# Schematic_v3.net
KiCad netlist of a schematic drawn in EAGLE
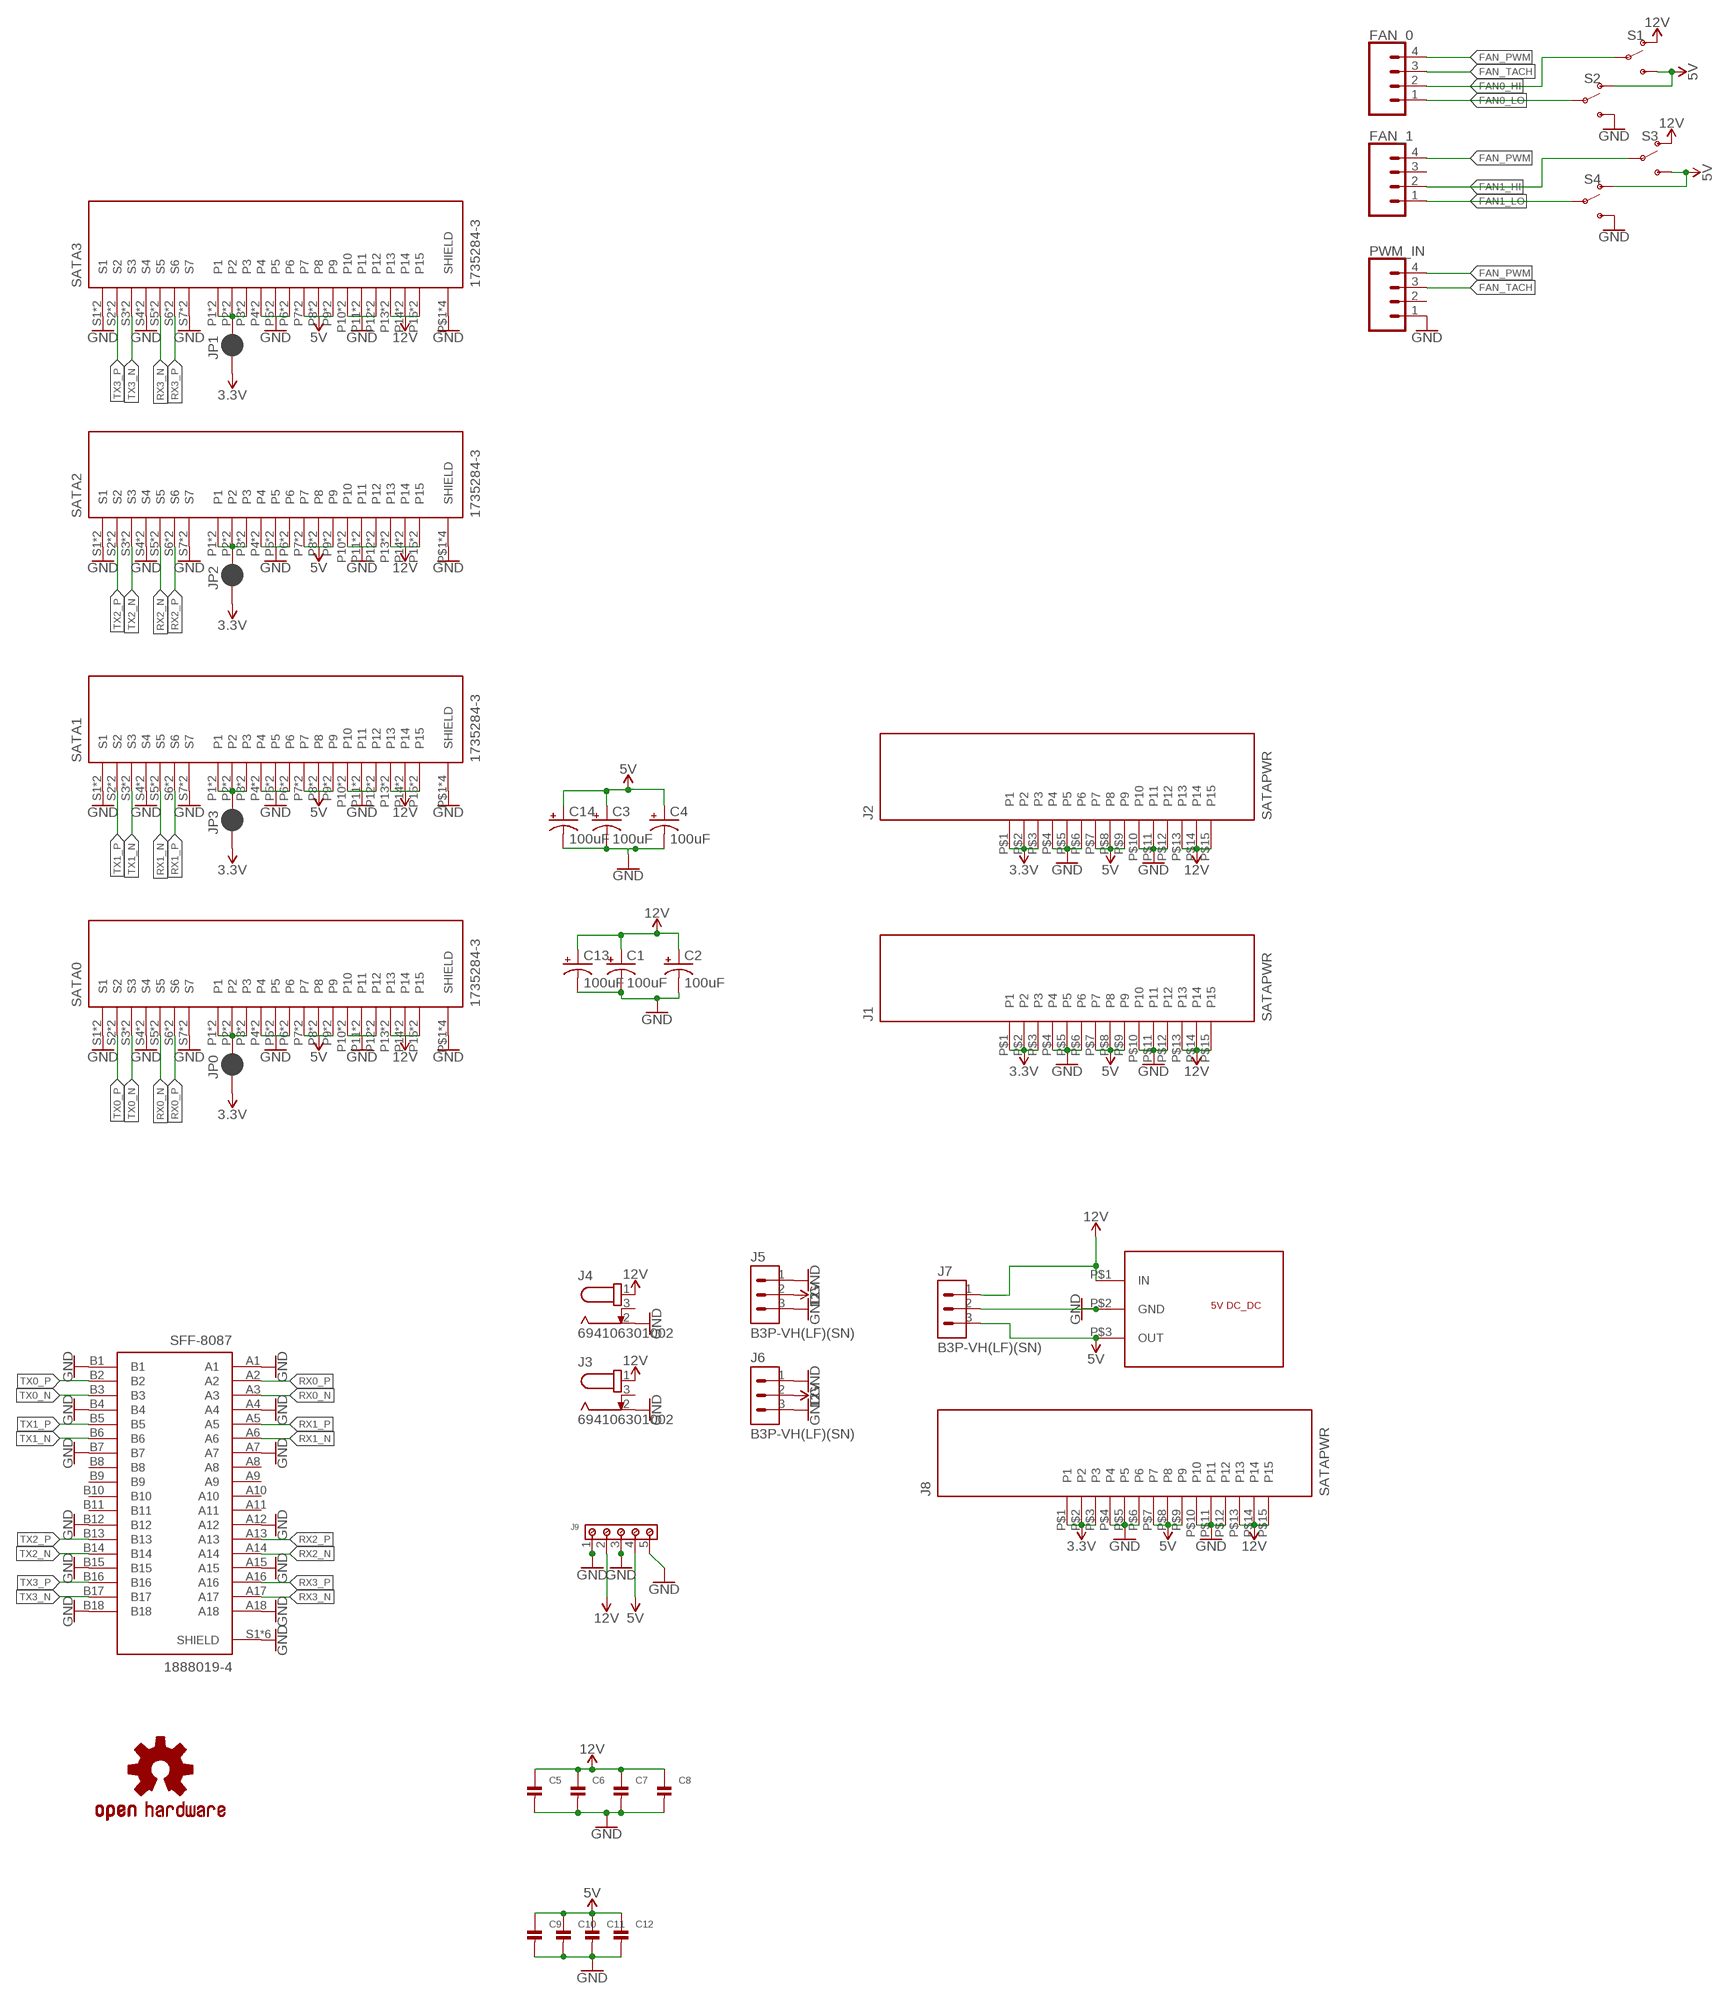
[diagram p0: schematic, sheet 1]

(export (version "E")
  (design (tool "Eeschema 10.0.6"))
  (components
    (comp (ref "C1")
      (value "100uF")
      (footprint "eagle-import:PANASONIC_D")
      (libsource (lib "eagle-import") (part "100UF-POLAR-25V-20%(ELEC)"))
    )
    (comp (ref "C2")
      (value "100uF")
      (footprint "eagle-import:PANASONIC_D")
      (libsource (lib "eagle-import") (part "100UF-POLAR-25V-20%(ELEC)"))
    )
    (comp (ref "C3")
      (value "100uF")
      (footprint "eagle-import:PANASONIC_D")
      (libsource (lib "eagle-import") (part "100UF-POLAR-25V-20%(ELEC)"))
    )
    (comp (ref "C4")
      (value "100uF")
      (footprint "eagle-import:PANASONIC_D")
      (libsource (lib "eagle-import") (part "100UF-POLAR-25V-20%(ELEC)"))
    )
    (comp (ref "C5")
      (value "CAP_CERAMIC0805")
      (footprint "eagle-import:C0805")
      (libsource (lib "eagle-import") (part "CAP_CERAMIC0805"))
    )
    (comp (ref "C6")
      (value "CAP_CERAMIC0805")
      (footprint "eagle-import:C0805")
      (libsource (lib "eagle-import") (part "CAP_CERAMIC0805"))
    )
    (comp (ref "C7")
      (value "CAP_CERAMIC0805")
      (footprint "eagle-import:C0805")
      (libsource (lib "eagle-import") (part "CAP_CERAMIC0805"))
    )
    (comp (ref "C8")
      (value "CAP_CERAMIC0805")
      (footprint "eagle-import:C0805")
      (libsource (lib "eagle-import") (part "CAP_CERAMIC0805"))
    )
    (comp (ref "C9")
      (value "CAP_CERAMIC0805")
      (footprint "eagle-import:C0805")
      (libsource (lib "eagle-import") (part "CAP_CERAMIC0805"))
    )
    (comp (ref "C10")
      (value "CAP_CERAMIC0805")
      (footprint "eagle-import:C0805")
      (libsource (lib "eagle-import") (part "CAP_CERAMIC0805"))
    )
    (comp (ref "C11")
      (value "CAP_CERAMIC0805")
      (footprint "eagle-import:C0805")
      (libsource (lib "eagle-import") (part "CAP_CERAMIC0805"))
    )
    (comp (ref "C12")
      (value "CAP_CERAMIC0805")
      (footprint "eagle-import:C0805")
      (libsource (lib "eagle-import") (part "CAP_CERAMIC0805"))
    )
    (comp (ref "C13")
      (value "100uF")
      (footprint "eagle-import:PANASONIC_D")
      (libsource (lib "eagle-import") (part "100UF-POLAR-25V-20%(ELEC)"))
    )
    (comp (ref "C14")
      (value "100uF")
      (footprint "eagle-import:PANASONIC_D")
      (libsource (lib "eagle-import") (part "100UF-POLAR-25V-20%(ELEC)"))
    )
    (comp (ref "FAN_0")
      (value "CONN_04POLAR_LOCK")
      (footprint "eagle-import:MOLEX-1X4_LOCK")
      (libsource (lib "eagle-import") (part "CONN_04POLAR_LOCK"))
    )
    (comp (ref "FAN_1")
      (value "CONN_04POLAR_LOCK")
      (footprint "eagle-import:MOLEX-1X4_LOCK")
      (libsource (lib "eagle-import") (part "CONN_04POLAR_LOCK"))
    )
    (comp (ref "J1")
      (value "SATAPWR")
      (footprint "eagle-import:PTH_90")
      (libsource (lib "eagle-import") (part "SATAPWR"))
    )
    (comp (ref "J2")
      (value "SATAPWR")
      (footprint "eagle-import:PTH_90")
      (libsource (lib "eagle-import") (part "SATAPWR"))
    )
    (comp (ref "J3")
      (value "694106301002")
      (footprint "eagle-import:694106301002")
      (fields
        (field (name "DIGIKEY_PART_NUMBER") "732-5930-ND")
        (field (name "MANUFACTURER") "Wurth Electronics Inc.")
        (field (name "CREATED_BY") "PCBLayout.com")
      )
      (libsource (lib "eagle-import") (part "694106301002"))
    )
    (comp (ref "J4")
      (value "694106301002")
      (footprint "eagle-import:694106301002")
      (fields
        (field (name "DIGIKEY_PART_NUMBER") "732-5930-ND")
        (field (name "MANUFACTURER") "Wurth Electronics Inc.")
        (field (name "CREATED_BY") "PCBLayout.com")
      )
      (libsource (lib "eagle-import") (part "694106301002"))
    )
    (comp (ref "J5")
      (value "B3P-VH(LF)(SN)")
      (footprint "eagle-import:HDR-03")
      (fields
        (field (name "DIGIKEY_PART_NUMBER") "455-1640-ND")
        (field (name "MANUFACTURER") "JST Sales America Inc.")
        (field (name "CREATED_BY") "PCBLayout.com")
      )
      (libsource (lib "eagle-import") (part "B3P-VH(LF)(SN)"))
    )
    (comp (ref "J6")
      (value "B3P-VH(LF)(SN)")
      (footprint "eagle-import:HDR-03")
      (fields
        (field (name "DIGIKEY_PART_NUMBER") "455-1640-ND")
        (field (name "MANUFACTURER") "JST Sales America Inc.")
        (field (name "CREATED_BY") "PCBLayout.com")
      )
      (libsource (lib "eagle-import") (part "B3P-VH(LF)(SN)"))
    )
    (comp (ref "J7")
      (value "B3P-VH(LF)(SN)")
      (footprint "eagle-import:HDR-03")
      (fields
        (field (name "DIGIKEY_PART_NUMBER") "455-1640-ND")
        (field (name "MANUFACTURER") "JST Sales America Inc.")
        (field (name "CREATED_BY") "PCBLayout.com")
      )
      (libsource (lib "eagle-import") (part "B3P-VH(LF)(SN)"))
    )
    (comp (ref "J8")
      (value "SATAPWR")
      (footprint "eagle-import:PTH_90")
      (libsource (lib "eagle-import") (part "SATAPWR"))
    )
    (comp (ref "J9")
      (value "691243410005")
      (footprint "eagle-import:691243410005")
      (libsource (lib "eagle-import") (part "691243410005"))
    )
    (comp (ref "JP0")
      (value "JUMPER-SMT_2_NC_PASTE_SILK")
      (footprint "eagle-import:SMT-JUMPER_2_NC_PASTE_SILK")
      (libsource (lib "eagle-import") (part "JUMPER-SMT_2_NC_PASTE_SILK"))
    )
    (comp (ref "JP1")
      (value "JUMPER-SMT_2_NC_PASTE_SILK")
      (footprint "eagle-import:SMT-JUMPER_2_NC_PASTE_SILK")
      (libsource (lib "eagle-import") (part "JUMPER-SMT_2_NC_PASTE_SILK"))
    )
    (comp (ref "JP2")
      (value "JUMPER-SMT_2_NC_PASTE_SILK")
      (footprint "eagle-import:SMT-JUMPER_2_NC_PASTE_SILK")
      (libsource (lib "eagle-import") (part "JUMPER-SMT_2_NC_PASTE_SILK"))
    )
    (comp (ref "JP3")
      (value "JUMPER-SMT_2_NC_PASTE_SILK")
      (footprint "eagle-import:SMT-JUMPER_2_NC_PASTE_SILK")
      (libsource (lib "eagle-import") (part "JUMPER-SMT_2_NC_PASTE_SILK"))
    )
    (comp (ref "LOGO1")
      (value "OSHW-LOGOL")
      (footprint "eagle-import:OSHW-LOGO-L")
      (libsource (lib "eagle-import") (part "OSHW-LOGOL"))
    )
    (comp (ref "PWM_IN")
      (value "CONN_04POLAR_LOCK")
      (footprint "eagle-import:MOLEX-1X4_LOCK")
      (libsource (lib "eagle-import") (part "CONN_04POLAR_LOCK"))
    )
    (comp (ref "S1")
      (value "SWITCH-SPDT-PTH-11.6X4.0MM-LOCK")
      (footprint "eagle-import:SWITCH_SPDT_PTH_11.6X4.0MM_LOCK")
      (libsource (lib "eagle-import") (part "SWITCH-SPDT-PTH-11.6X4.0MM-LOCK"))
    )
    (comp (ref "S2")
      (value "SWITCH-SPDT-PTH-11.6X4.0MM-LOCK")
      (footprint "eagle-import:SWITCH_SPDT_PTH_11.6X4.0MM_LOCK")
      (libsource (lib "eagle-import") (part "SWITCH-SPDT-PTH-11.6X4.0MM-LOCK"))
    )
    (comp (ref "S3")
      (value "SWITCH-SPDT-PTH-11.6X4.0MM-LOCK")
      (footprint "eagle-import:SWITCH_SPDT_PTH_11.6X4.0MM_LOCK")
      (libsource (lib "eagle-import") (part "SWITCH-SPDT-PTH-11.6X4.0MM-LOCK"))
    )
    (comp (ref "S4")
      (value "SWITCH-SPDT-PTH-11.6X4.0MM-LOCK")
      (footprint "eagle-import:SWITCH_SPDT_PTH_11.6X4.0MM_LOCK")
      (libsource (lib "eagle-import") (part "SWITCH-SPDT-PTH-11.6X4.0MM-LOCK"))
    )
    (comp (ref "SATA0")
      (value "1735284-3")
      (footprint "eagle-import:TE_2023246-2")
      (fields (field (name "COMMENT") "2023246-2") (field (name "MF") "TE Connectivity"))
      (libsource (lib "eagle-import") (part "2023246-21735284-3"))
    )
    (comp (ref "SATA1")
      (value "1735284-3")
      (footprint "eagle-import:TE_2023246-2")
      (fields (field (name "COMMENT") "2023246-2") (field (name "MF") "TE Connectivity"))
      (libsource (lib "eagle-import") (part "2023246-21735284-3"))
    )
    (comp (ref "SATA2")
      (value "1735284-3")
      (footprint "eagle-import:TE_2023246-2")
      (fields (field (name "COMMENT") "2023246-2") (field (name "MF") "TE Connectivity"))
      (libsource (lib "eagle-import") (part "2023246-21735284-3"))
    )
    (comp (ref "SATA3")
      (value "1735284-3")
      (footprint "eagle-import:TE_2023246-2")
      (fields (field (name "COMMENT") "2023246-2") (field (name "MF") "TE Connectivity"))
      (libsource (lib "eagle-import") (part "2023246-21735284-3"))
    )
    (comp (ref "SFF-8087")
      (value "1888019-4")
      (footprint "eagle-import:TE_1888019-4")
      (fields (field (name "MF") "TE Connectivity"))
      (libsource (lib "eagle-import") (part "1888019-4"))
    )
    (comp (ref "U$1")
      (value "5V_DC_DC")
      (footprint "eagle-import:5V_15W_DC_DC")
      (libsource (lib "eagle-import") (part "5V_DC_DC"))
    )
  )
  (nets
    (net (code "1") (name "3.3V") (class "Default")
      (node (ref "J1") (pin "P$1") (pinfunction "P1_P$1") (pintype "passive"))
      (node (ref "J1") (pin "P$2") (pinfunction "P2_P$2") (pintype "passive"))
      (node (ref "J1") (pin "P$3") (pinfunction "P3_P$3") (pintype "passive"))
      (node (ref "J2") (pin "P$1") (pinfunction "P1_P$1") (pintype "passive"))
      (node (ref "J2") (pin "P$2") (pinfunction "P2_P$2") (pintype "passive"))
      (node (ref "J2") (pin "P$3") (pinfunction "P3_P$3") (pintype "passive"))
      (node (ref "J8") (pin "P$1") (pinfunction "P1_P$1") (pintype "passive"))
      (node (ref "J8") (pin "P$2") (pinfunction "P2_P$2") (pintype "passive"))
      (node (ref "J8") (pin "P$3") (pinfunction "P3_P$3") (pintype "passive"))
      (node (ref "JP0") (pin "1") (pinfunction "1_1") (pintype "passive"))
      (node (ref "JP1") (pin "1") (pinfunction "1_1") (pintype "passive"))
      (node (ref "JP2") (pin "1") (pinfunction "1_1") (pintype "passive"))
      (node (ref "JP3") (pin "1") (pinfunction "1_1") (pintype "passive"))
    )
    (net (code "2") (name "5V") (class "Default")
      (node (ref "C10") (pin "1") (pinfunction "P$1_1") (pintype "passive"))
      (node (ref "C11") (pin "1") (pinfunction "P$1_1") (pintype "passive"))
      (node (ref "C12") (pin "1") (pinfunction "P$1_1") (pintype "passive"))
      (node (ref "C14") (pin "+") (pinfunction "+_+") (pintype "passive"))
      (node (ref "C3") (pin "+") (pinfunction "+_+") (pintype "passive"))
      (node (ref "C4") (pin "+") (pinfunction "+_+") (pintype "passive"))
      (node (ref "C9") (pin "1") (pinfunction "P$1_1") (pintype "passive"))
      (node (ref "J1") (pin "P$7") (pinfunction "P7_P$7") (pintype "passive"))
      (node (ref "J1") (pin "P$8") (pinfunction "P8_P$8") (pintype "passive"))
      (node (ref "J1") (pin "P$9") (pinfunction "P9_P$9") (pintype "passive"))
      (node (ref "J2") (pin "P$7") (pinfunction "P7_P$7") (pintype "passive"))
      (node (ref "J2") (pin "P$8") (pinfunction "P8_P$8") (pintype "passive"))
      (node (ref "J2") (pin "P$9") (pinfunction "P9_P$9") (pintype "passive"))
      (node (ref "J7") (pin "3") (pinfunction "3_3") (pintype "passive"))
      (node (ref "J8") (pin "P$7") (pinfunction "P7_P$7") (pintype "passive"))
      (node (ref "J8") (pin "P$8") (pinfunction "P8_P$8") (pintype "passive"))
      (node (ref "J8") (pin "P$9") (pinfunction "P9_P$9") (pintype "passive"))
      (node (ref "J9") (pin "4") (pinfunction "4_4") (pintype "passive"))
      (node (ref "S1") (pin "3") (pinfunction "S_3") (pintype "passive"))
      (node (ref "S2") (pin "1") (pinfunction "O_1") (pintype "passive"))
      (node (ref "S3") (pin "3") (pinfunction "S_3") (pintype "passive"))
      (node (ref "S4") (pin "1") (pinfunction "O_1") (pintype "passive"))
      (node (ref "SATA0") (pin "P7") (pinfunction "P7_P7") (pintype "passive"))
      (node (ref "SATA0") (pin "P8") (pinfunction "P8_P8") (pintype "passive"))
      (node (ref "SATA0") (pin "P9") (pinfunction "P9_P9") (pintype "passive"))
      (node (ref "SATA0") (pin "THT14") (pinfunction "P7_THT14") (pintype "passive"))
      (node (ref "SATA0") (pin "THT15") (pinfunction "P8_THT15") (pintype "passive"))
      (node (ref "SATA0") (pin "THT16") (pinfunction "P9_THT16") (pintype "passive"))
      (node (ref "SATA1") (pin "P7") (pinfunction "P7_P7") (pintype "passive"))
      (node (ref "SATA1") (pin "P8") (pinfunction "P8_P8") (pintype "passive"))
      (node (ref "SATA1") (pin "P9") (pinfunction "P9_P9") (pintype "passive"))
      (node (ref "SATA1") (pin "THT14") (pinfunction "P7_THT14") (pintype "passive"))
      (node (ref "SATA1") (pin "THT15") (pinfunction "P8_THT15") (pintype "passive"))
      (node (ref "SATA1") (pin "THT16") (pinfunction "P9_THT16") (pintype "passive"))
      (node (ref "SATA2") (pin "P7") (pinfunction "P7_P7") (pintype "passive"))
      (node (ref "SATA2") (pin "P8") (pinfunction "P8_P8") (pintype "passive"))
      (node (ref "SATA2") (pin "P9") (pinfunction "P9_P9") (pintype "passive"))
      (node (ref "SATA2") (pin "THT14") (pinfunction "P7_THT14") (pintype "passive"))
      (node (ref "SATA2") (pin "THT15") (pinfunction "P8_THT15") (pintype "passive"))
      (node (ref "SATA2") (pin "THT16") (pinfunction "P9_THT16") (pintype "passive"))
      (node (ref "SATA3") (pin "P7") (pinfunction "P7_P7") (pintype "passive"))
      (node (ref "SATA3") (pin "P8") (pinfunction "P8_P8") (pintype "passive"))
      (node (ref "SATA3") (pin "P9") (pinfunction "P9_P9") (pintype "passive"))
      (node (ref "SATA3") (pin "THT14") (pinfunction "P7_THT14") (pintype "passive"))
      (node (ref "SATA3") (pin "THT15") (pinfunction "P8_THT15") (pintype "passive"))
      (node (ref "SATA3") (pin "THT16") (pinfunction "P9_THT16") (pintype "passive"))
      (node (ref "U$1") (pin "P$3") (pinfunction "OUT_P$3") (pintype "bidirectional"))
    )
    (net (code "3") (name "12V") (class "Default")
      (node (ref "C1") (pin "+") (pinfunction "+_+") (pintype "passive"))
      (node (ref "C13") (pin "+") (pinfunction "+_+") (pintype "passive"))
      (node (ref "C2") (pin "+") (pinfunction "+_+") (pintype "passive"))
      (node (ref "C5") (pin "1") (pinfunction "P$1_1") (pintype "passive"))
      (node (ref "C6") (pin "1") (pinfunction "P$1_1") (pintype "passive"))
      (node (ref "C7") (pin "1") (pinfunction "P$1_1") (pintype "passive"))
      (node (ref "C8") (pin "1") (pinfunction "P$1_1") (pintype "passive"))
      (node (ref "J1") (pin "P$13") (pinfunction "P13_P$13") (pintype "passive"))
      (node (ref "J1") (pin "P$14") (pinfunction "P14_P$14") (pintype "passive"))
      (node (ref "J1") (pin "P$15") (pinfunction "P15_P$15") (pintype "passive"))
      (node (ref "J2") (pin "P$13") (pinfunction "P13_P$13") (pintype "passive"))
      (node (ref "J2") (pin "P$14") (pinfunction "P14_P$14") (pintype "passive"))
      (node (ref "J2") (pin "P$15") (pinfunction "P15_P$15") (pintype "passive"))
      (node (ref "J3") (pin "1") (pinfunction "1_1") (pintype "passive"))
      (node (ref "J4") (pin "1") (pinfunction "1_1") (pintype "passive"))
      (node (ref "J5") (pin "2") (pinfunction "2_2") (pintype "passive"))
      (node (ref "J6") (pin "2") (pinfunction "2_2") (pintype "passive"))
      (node (ref "J7") (pin "1") (pinfunction "1_1") (pintype "passive"))
      (node (ref "J8") (pin "P$13") (pinfunction "P13_P$13") (pintype "passive"))
      (node (ref "J8") (pin "P$14") (pinfunction "P14_P$14") (pintype "passive"))
      (node (ref "J8") (pin "P$15") (pinfunction "P15_P$15") (pintype "passive"))
      (node (ref "J9") (pin "2") (pinfunction "2_2") (pintype "passive"))
      (node (ref "S1") (pin "1") (pinfunction "O_1") (pintype "passive"))
      (node (ref "S3") (pin "1") (pinfunction "O_1") (pintype "passive"))
      (node (ref "SATA0") (pin "P13") (pinfunction "P13_P13") (pintype "passive"))
      (node (ref "SATA0") (pin "P14") (pinfunction "P14_P14") (pintype "passive"))
      (node (ref "SATA0") (pin "P15") (pinfunction "P15_P15") (pintype "passive"))
      (node (ref "SATA0") (pin "THT20") (pinfunction "P13_THT20") (pintype "passive"))
      (node (ref "SATA0") (pin "THT21") (pinfunction "P14_THT21") (pintype "passive"))
      (node (ref "SATA0") (pin "THT22") (pinfunction "P15_THT22") (pintype "passive"))
      (node (ref "SATA1") (pin "P13") (pinfunction "P13_P13") (pintype "passive"))
      (node (ref "SATA1") (pin "P14") (pinfunction "P14_P14") (pintype "passive"))
      (node (ref "SATA1") (pin "P15") (pinfunction "P15_P15") (pintype "passive"))
      (node (ref "SATA1") (pin "THT20") (pinfunction "P13_THT20") (pintype "passive"))
      (node (ref "SATA1") (pin "THT21") (pinfunction "P14_THT21") (pintype "passive"))
      (node (ref "SATA1") (pin "THT22") (pinfunction "P15_THT22") (pintype "passive"))
      (node (ref "SATA2") (pin "P13") (pinfunction "P13_P13") (pintype "passive"))
      (node (ref "SATA2") (pin "P14") (pinfunction "P14_P14") (pintype "passive"))
      (node (ref "SATA2") (pin "P15") (pinfunction "P15_P15") (pintype "passive"))
      (node (ref "SATA2") (pin "THT20") (pinfunction "P13_THT20") (pintype "passive"))
      (node (ref "SATA2") (pin "THT21") (pinfunction "P14_THT21") (pintype "passive"))
      (node (ref "SATA2") (pin "THT22") (pinfunction "P15_THT22") (pintype "passive"))
      (node (ref "SATA3") (pin "P13") (pinfunction "P13_P13") (pintype "passive"))
      (node (ref "SATA3") (pin "P14") (pinfunction "P14_P14") (pintype "passive"))
      (node (ref "SATA3") (pin "P15") (pinfunction "P15_P15") (pintype "passive"))
      (node (ref "SATA3") (pin "THT20") (pinfunction "P13_THT20") (pintype "passive"))
      (node (ref "SATA3") (pin "THT21") (pinfunction "P14_THT21") (pintype "passive"))
      (node (ref "SATA3") (pin "THT22") (pinfunction "P15_THT22") (pintype "passive"))
      (node (ref "U$1") (pin "P$1") (pinfunction "IN_P$1") (pintype "bidirectional"))
    )
    (net (code "4") (name "FAN0_HI") (class "Default")
      (node (ref "FAN_0") (pin "2") (pinfunction "2_2") (pintype "passive"))
      (node (ref "S1") (pin "2") (pinfunction "P_2") (pintype "passive"))
    )
    (net (code "5") (name "FAN0_LO") (class "Default")
      (node (ref "FAN_0") (pin "1") (pinfunction "1_1") (pintype "passive"))
      (node (ref "S2") (pin "2") (pinfunction "P_2") (pintype "passive"))
    )
    (net (code "6") (name "FAN1_HI") (class "Default")
      (node (ref "FAN_1") (pin "2") (pinfunction "2_2") (pintype "passive"))
      (node (ref "S3") (pin "2") (pinfunction "P_2") (pintype "passive"))
    )
    (net (code "7") (name "FAN1_LO") (class "Default")
      (node (ref "FAN_1") (pin "1") (pinfunction "1_1") (pintype "passive"))
      (node (ref "S4") (pin "2") (pinfunction "P_2") (pintype "passive"))
    )
    (net (code "8") (name "FAN_PWM") (class "Default")
      (node (ref "FAN_0") (pin "4") (pinfunction "4_4") (pintype "passive"))
      (node (ref "FAN_1") (pin "4") (pinfunction "4_4") (pintype "passive"))
      (node (ref "PWM_IN") (pin "4") (pinfunction "4_4") (pintype "passive"))
    )
    (net (code "9") (name "FAN_TACH") (class "Default")
      (node (ref "FAN_0") (pin "3") (pinfunction "3_3") (pintype "passive"))
      (node (ref "PWM_IN") (pin "3") (pinfunction "3_3") (pintype "passive"))
    )
    (net (code "10") (name "GND") (class "Default")
      (node (ref "C1") (pin "-") (pinfunction "-_-") (pintype "passive"))
      (node (ref "C10") (pin "2") (pinfunction "P$2_2") (pintype "passive"))
      (node (ref "C11") (pin "2") (pinfunction "P$2_2") (pintype "passive"))
      (node (ref "C12") (pin "2") (pinfunction "P$2_2") (pintype "passive"))
      (node (ref "C13") (pin "-") (pinfunction "-_-") (pintype "passive"))
      (node (ref "C14") (pin "-") (pinfunction "-_-") (pintype "passive"))
      (node (ref "C2") (pin "-") (pinfunction "-_-") (pintype "passive"))
      (node (ref "C3") (pin "-") (pinfunction "-_-") (pintype "passive"))
      (node (ref "C4") (pin "-") (pinfunction "-_-") (pintype "passive"))
      (node (ref "C5") (pin "2") (pinfunction "P$2_2") (pintype "passive"))
      (node (ref "C6") (pin "2") (pinfunction "P$2_2") (pintype "passive"))
      (node (ref "C7") (pin "2") (pinfunction "P$2_2") (pintype "passive"))
      (node (ref "C8") (pin "2") (pinfunction "P$2_2") (pintype "passive"))
      (node (ref "C9") (pin "2") (pinfunction "P$2_2") (pintype "passive"))
      (node (ref "J1") (pin "P$10") (pinfunction "P10_P$10") (pintype "passive"))
      (node (ref "J1") (pin "P$11") (pinfunction "P11_P$11") (pintype "passive"))
      (node (ref "J1") (pin "P$12") (pinfunction "P12_P$12") (pintype "passive"))
      (node (ref "J1") (pin "P$4") (pinfunction "P4_P$4") (pintype "passive"))
      (node (ref "J1") (pin "P$5") (pinfunction "P5_P$5") (pintype "passive"))
      (node (ref "J1") (pin "P$6") (pinfunction "P6_P$6") (pintype "passive"))
      (node (ref "J2") (pin "P$10") (pinfunction "P10_P$10") (pintype "passive"))
      (node (ref "J2") (pin "P$11") (pinfunction "P11_P$11") (pintype "passive"))
      (node (ref "J2") (pin "P$12") (pinfunction "P12_P$12") (pintype "passive"))
      (node (ref "J2") (pin "P$4") (pinfunction "P4_P$4") (pintype "passive"))
      (node (ref "J2") (pin "P$5") (pinfunction "P5_P$5") (pintype "passive"))
      (node (ref "J2") (pin "P$6") (pinfunction "P6_P$6") (pintype "passive"))
      (node (ref "J3") (pin "2") (pinfunction "2_2") (pintype "passive"))
      (node (ref "J4") (pin "2") (pinfunction "2_2") (pintype "passive"))
      (node (ref "J5") (pin "1") (pinfunction "1_1") (pintype "passive"))
      (node (ref "J5") (pin "3") (pinfunction "3_3") (pintype "passive"))
      (node (ref "J6") (pin "1") (pinfunction "1_1") (pintype "passive"))
      (node (ref "J6") (pin "3") (pinfunction "3_3") (pintype "passive"))
      (node (ref "J7") (pin "2") (pinfunction "2_2") (pintype "passive"))
      (node (ref "J8") (pin "P$10") (pinfunction "P10_P$10") (pintype "passive"))
      (node (ref "J8") (pin "P$11") (pinfunction "P11_P$11") (pintype "passive"))
      (node (ref "J8") (pin "P$12") (pinfunction "P12_P$12") (pintype "passive"))
      (node (ref "J8") (pin "P$4") (pinfunction "P4_P$4") (pintype "passive"))
      (node (ref "J8") (pin "P$5") (pinfunction "P5_P$5") (pintype "passive"))
      (node (ref "J8") (pin "P$6") (pinfunction "P6_P$6") (pintype "passive"))
      (node (ref "J9") (pin "1") (pinfunction "1_1") (pintype "passive"))
      (node (ref "J9") (pin "3") (pinfunction "3_3") (pintype "passive"))
      (node (ref "J9") (pin "5") (pinfunction "5_5") (pintype "passive"))
      (node (ref "PWM_IN") (pin "1") (pinfunction "1_1") (pintype "passive"))
      (node (ref "S2") (pin "3") (pinfunction "S_3") (pintype "passive"))
      (node (ref "S4") (pin "3") (pinfunction "S_3") (pintype "passive"))
      (node (ref "SATA0") (pin "P$1") (pinfunction "SHIELD_P$1") (pintype "passive"))
      (node (ref "SATA0") (pin "P$2") (pinfunction "SHIELD_P$2") (pintype "passive"))
      (node (ref "SATA0") (pin "P10") (pinfunction "P10_P10") (pintype "passive"))
      (node (ref "SATA0") (pin "P11") (pinfunction "P11_P11") (pintype "passive"))
      (node (ref "SATA0") (pin "P12") (pinfunction "P12_P12") (pintype "passive"))
      (node (ref "SATA0") (pin "P4") (pinfunction "P4_P4") (pintype "passive"))
      (node (ref "SATA0") (pin "P5") (pinfunction "P5_P5") (pintype "passive"))
      (node (ref "SATA0") (pin "P6") (pinfunction "P6_P6") (pintype "passive"))
      (node (ref "SATA0") (pin "S1") (pinfunction "S1_S1") (pintype "passive"))
      (node (ref "SATA0") (pin "S4") (pinfunction "S4_S4") (pintype "passive"))
      (node (ref "SATA0") (pin "S7") (pinfunction "S7_S7") (pintype "passive"))
      (node (ref "SATA0") (pin "THT$1") (pinfunction "SHIELD_THT$1") (pintype "passive"))
      (node (ref "SATA0") (pin "THT$2") (pinfunction "SHIELD_THT$2") (pintype "passive"))
      (node (ref "SATA0") (pin "THT1") (pinfunction "S1_THT1") (pintype "passive"))
      (node (ref "SATA0") (pin "THT11") (pinfunction "P4_THT11") (pintype "passive"))
      (node (ref "SATA0") (pin "THT12") (pinfunction "P5_THT12") (pintype "passive"))
      (node (ref "SATA0") (pin "THT13") (pinfunction "P6_THT13") (pintype "passive"))
      (node (ref "SATA0") (pin "THT17") (pinfunction "P10_THT17") (pintype "passive"))
      (node (ref "SATA0") (pin "THT18") (pinfunction "P11_THT18") (pintype "passive"))
      (node (ref "SATA0") (pin "THT19") (pinfunction "P12_THT19") (pintype "passive"))
      (node (ref "SATA0") (pin "THT4") (pinfunction "S4_THT4") (pintype "passive"))
      (node (ref "SATA0") (pin "THT7") (pinfunction "S7_THT7") (pintype "passive"))
      (node (ref "SATA1") (pin "P$1") (pinfunction "SHIELD_P$1") (pintype "passive"))
      (node (ref "SATA1") (pin "P$2") (pinfunction "SHIELD_P$2") (pintype "passive"))
      (node (ref "SATA1") (pin "P10") (pinfunction "P10_P10") (pintype "passive"))
      (node (ref "SATA1") (pin "P11") (pinfunction "P11_P11") (pintype "passive"))
      (node (ref "SATA1") (pin "P12") (pinfunction "P12_P12") (pintype "passive"))
      (node (ref "SATA1") (pin "P4") (pinfunction "P4_P4") (pintype "passive"))
      (node (ref "SATA1") (pin "P5") (pinfunction "P5_P5") (pintype "passive"))
      (node (ref "SATA1") (pin "P6") (pinfunction "P6_P6") (pintype "passive"))
      (node (ref "SATA1") (pin "S1") (pinfunction "S1_S1") (pintype "passive"))
      (node (ref "SATA1") (pin "S4") (pinfunction "S4_S4") (pintype "passive"))
      (node (ref "SATA1") (pin "S7") (pinfunction "S7_S7") (pintype "passive"))
      (node (ref "SATA1") (pin "THT$1") (pinfunction "SHIELD_THT$1") (pintype "passive"))
      (node (ref "SATA1") (pin "THT$2") (pinfunction "SHIELD_THT$2") (pintype "passive"))
      (node (ref "SATA1") (pin "THT1") (pinfunction "S1_THT1") (pintype "passive"))
      (node (ref "SATA1") (pin "THT11") (pinfunction "P4_THT11") (pintype "passive"))
      (node (ref "SATA1") (pin "THT12") (pinfunction "P5_THT12") (pintype "passive"))
      (node (ref "SATA1") (pin "THT13") (pinfunction "P6_THT13") (pintype "passive"))
      (node (ref "SATA1") (pin "THT17") (pinfunction "P10_THT17") (pintype "passive"))
      (node (ref "SATA1") (pin "THT18") (pinfunction "P11_THT18") (pintype "passive"))
      (node (ref "SATA1") (pin "THT19") (pinfunction "P12_THT19") (pintype "passive"))
      (node (ref "SATA1") (pin "THT4") (pinfunction "S4_THT4") (pintype "passive"))
      (node (ref "SATA1") (pin "THT7") (pinfunction "S7_THT7") (pintype "passive"))
      (node (ref "SATA2") (pin "P$1") (pinfunction "SHIELD_P$1") (pintype "passive"))
      (node (ref "SATA2") (pin "P$2") (pinfunction "SHIELD_P$2") (pintype "passive"))
      (node (ref "SATA2") (pin "P10") (pinfunction "P10_P10") (pintype "passive"))
      (node (ref "SATA2") (pin "P11") (pinfunction "P11_P11") (pintype "passive"))
      (node (ref "SATA2") (pin "P12") (pinfunction "P12_P12") (pintype "passive"))
      (node (ref "SATA2") (pin "P4") (pinfunction "P4_P4") (pintype "passive"))
      (node (ref "SATA2") (pin "P5") (pinfunction "P5_P5") (pintype "passive"))
      (node (ref "SATA2") (pin "P6") (pinfunction "P6_P6") (pintype "passive"))
      (node (ref "SATA2") (pin "S1") (pinfunction "S1_S1") (pintype "passive"))
      (node (ref "SATA2") (pin "S4") (pinfunction "S4_S4") (pintype "passive"))
      (node (ref "SATA2") (pin "S7") (pinfunction "S7_S7") (pintype "passive"))
      (node (ref "SATA2") (pin "THT$1") (pinfunction "SHIELD_THT$1") (pintype "passive"))
      (node (ref "SATA2") (pin "THT$2") (pinfunction "SHIELD_THT$2") (pintype "passive"))
      (node (ref "SATA2") (pin "THT1") (pinfunction "S1_THT1") (pintype "passive"))
      (node (ref "SATA2") (pin "THT11") (pinfunction "P4_THT11") (pintype "passive"))
      (node (ref "SATA2") (pin "THT12") (pinfunction "P5_THT12") (pintype "passive"))
      (node (ref "SATA2") (pin "THT13") (pinfunction "P6_THT13") (pintype "passive"))
      (node (ref "SATA2") (pin "THT17") (pinfunction "P10_THT17") (pintype "passive"))
      (node (ref "SATA2") (pin "THT18") (pinfunction "P11_THT18") (pintype "passive"))
      (node (ref "SATA2") (pin "THT19") (pinfunction "P12_THT19") (pintype "passive"))
      (node (ref "SATA2") (pin "THT4") (pinfunction "S4_THT4") (pintype "passive"))
      (node (ref "SATA2") (pin "THT7") (pinfunction "S7_THT7") (pintype "passive"))
      (node (ref "SATA3") (pin "P$1") (pinfunction "SHIELD_P$1") (pintype "passive"))
      (node (ref "SATA3") (pin "P$2") (pinfunction "SHIELD_P$2") (pintype "passive"))
      (node (ref "SATA3") (pin "P10") (pinfunction "P10_P10") (pintype "passive"))
      (node (ref "SATA3") (pin "P11") (pinfunction "P11_P11") (pintype "passive"))
      (node (ref "SATA3") (pin "P12") (pinfunction "P12_P12") (pintype "passive"))
      (node (ref "SATA3") (pin "P4") (pinfunction "P4_P4") (pintype "passive"))
      (node (ref "SATA3") (pin "P5") (pinfunction "P5_P5") (pintype "passive"))
      (node (ref "SATA3") (pin "P6") (pinfunction "P6_P6") (pintype "passive"))
      (node (ref "SATA3") (pin "S1") (pinfunction "S1_S1") (pintype "passive"))
      (node (ref "SATA3") (pin "S4") (pinfunction "S4_S4") (pintype "passive"))
      (node (ref "SATA3") (pin "S7") (pinfunction "S7_S7") (pintype "passive"))
      (node (ref "SATA3") (pin "THT$1") (pinfunction "SHIELD_THT$1") (pintype "passive"))
      (node (ref "SATA3") (pin "THT$2") (pinfunction "SHIELD_THT$2") (pintype "passive"))
      (node (ref "SATA3") (pin "THT1") (pinfunction "S1_THT1") (pintype "passive"))
      (node (ref "SATA3") (pin "THT11") (pinfunction "P4_THT11") (pintype "passive"))
      (node (ref "SATA3") (pin "THT12") (pinfunction "P5_THT12") (pintype "passive"))
      (node (ref "SATA3") (pin "THT13") (pinfunction "P6_THT13") (pintype "passive"))
      (node (ref "SATA3") (pin "THT17") (pinfunction "P10_THT17") (pintype "passive"))
      (node (ref "SATA3") (pin "THT18") (pinfunction "P11_THT18") (pintype "passive"))
      (node (ref "SATA3") (pin "THT19") (pinfunction "P12_THT19") (pintype "passive"))
      (node (ref "SATA3") (pin "THT4") (pinfunction "S4_THT4") (pintype "passive"))
      (node (ref "SATA3") (pin "THT7") (pinfunction "S7_THT7") (pintype "passive"))
      (node (ref "SFF-8087") (pin "A1") (pinfunction "A1_A1") (pintype "passive"))
      (node (ref "SFF-8087") (pin "A12") (pinfunction "A12_A12") (pintype "passive"))
      (node (ref "SFF-8087") (pin "A15") (pinfunction "A15_A15") (pintype "passive"))
      (node (ref "SFF-8087") (pin "A18") (pinfunction "A18_A18") (pintype "passive"))
      (node (ref "SFF-8087") (pin "A4") (pinfunction "A4_A4") (pintype "passive"))
      (node (ref "SFF-8087") (pin "A7") (pinfunction "A7_A7") (pintype "passive"))
      (node (ref "SFF-8087") (pin "B1") (pinfunction "B1_B1") (pintype "passive"))
      (node (ref "SFF-8087") (pin "B12") (pinfunction "B12_B12") (pintype "passive"))
      (node (ref "SFF-8087") (pin "B15") (pinfunction "B15_B15") (pintype "passive"))
      (node (ref "SFF-8087") (pin "B18") (pinfunction "B18_B18") (pintype "passive"))
      (node (ref "SFF-8087") (pin "B4") (pinfunction "B4_B4") (pintype "passive"))
      (node (ref "SFF-8087") (pin "B7") (pinfunction "B7_B7") (pintype "passive"))
      (node (ref "SFF-8087") (pin "S1") (pinfunction "SHIELD_S1") (pintype "passive"))
      (node (ref "SFF-8087") (pin "S2") (pinfunction "SHIELD_S2") (pintype "passive"))
      (node (ref "SFF-8087") (pin "S3") (pinfunction "SHIELD_S3") (pintype "passive"))
      (node (ref "SFF-8087") (pin "S4") (pinfunction "SHIELD_S4") (pintype "passive"))
      (node (ref "SFF-8087") (pin "S5") (pinfunction "SHIELD_S5") (pintype "passive"))
      (node (ref "SFF-8087") (pin "S6") (pinfunction "SHIELD_S6") (pintype "passive"))
      (node (ref "U$1") (pin "P$2") (pinfunction "GND_P$2") (pintype "bidirectional"))
    )
    (net (code "11") (name "Net-(JP0-Pad2)") (class "Default")
      (node (ref "JP0") (pin "2") (pinfunction "2_2") (pintype "passive"))
      (node (ref "SATA0") (pin "P1") (pinfunction "P1_P1") (pintype "passive"))
      (node (ref "SATA0") (pin "P2") (pinfunction "P2_P2") (pintype "passive"))
      (node (ref "SATA0") (pin "P3") (pinfunction "P3_P3") (pintype "passive"))
      (node (ref "SATA0") (pin "THT10") (pinfunction "P3_THT10") (pintype "passive"))
      (node (ref "SATA0") (pin "THT8") (pinfunction "P1_THT8") (pintype "passive"))
      (node (ref "SATA0") (pin "THT9") (pinfunction "P2_THT9") (pintype "passive"))
    )
    (net (code "12") (name "Net-(JP1-Pad2)") (class "Default")
      (node (ref "JP1") (pin "2") (pinfunction "2_2") (pintype "passive"))
      (node (ref "SATA3") (pin "P1") (pinfunction "P1_P1") (pintype "passive"))
      (node (ref "SATA3") (pin "P2") (pinfunction "P2_P2") (pintype "passive"))
      (node (ref "SATA3") (pin "P3") (pinfunction "P3_P3") (pintype "passive"))
      (node (ref "SATA3") (pin "THT10") (pinfunction "P3_THT10") (pintype "passive"))
      (node (ref "SATA3") (pin "THT8") (pinfunction "P1_THT8") (pintype "passive"))
      (node (ref "SATA3") (pin "THT9") (pinfunction "P2_THT9") (pintype "passive"))
    )
    (net (code "13") (name "Net-(JP2-Pad2)") (class "Default")
      (node (ref "JP2") (pin "2") (pinfunction "2_2") (pintype "passive"))
      (node (ref "SATA2") (pin "P1") (pinfunction "P1_P1") (pintype "passive"))
      (node (ref "SATA2") (pin "P2") (pinfunction "P2_P2") (pintype "passive"))
      (node (ref "SATA2") (pin "P3") (pinfunction "P3_P3") (pintype "passive"))
      (node (ref "SATA2") (pin "THT10") (pinfunction "P3_THT10") (pintype "passive"))
      (node (ref "SATA2") (pin "THT8") (pinfunction "P1_THT8") (pintype "passive"))
      (node (ref "SATA2") (pin "THT9") (pinfunction "P2_THT9") (pintype "passive"))
    )
    (net (code "14") (name "Net-(JP3-Pad2)") (class "Default")
      (node (ref "JP3") (pin "2") (pinfunction "2_2") (pintype "passive"))
      (node (ref "SATA1") (pin "P1") (pinfunction "P1_P1") (pintype "passive"))
      (node (ref "SATA1") (pin "P2") (pinfunction "P2_P2") (pintype "passive"))
      (node (ref "SATA1") (pin "P3") (pinfunction "P3_P3") (pintype "passive"))
      (node (ref "SATA1") (pin "THT10") (pinfunction "P3_THT10") (pintype "passive"))
      (node (ref "SATA1") (pin "THT8") (pinfunction "P1_THT8") (pintype "passive"))
      (node (ref "SATA1") (pin "THT9") (pinfunction "P2_THT9") (pintype "passive"))
    )
    (net (code "15") (name "RX0_N") (class "Default")
      (node (ref "SATA0") (pin "S5") (pinfunction "S5_S5") (pintype "passive"))
      (node (ref "SATA0") (pin "THT5") (pinfunction "S5_THT5") (pintype "passive"))
      (node (ref "SFF-8087") (pin "A3") (pinfunction "A3_A3") (pintype "passive"))
    )
    (net (code "16") (name "RX0_P") (class "Default")
      (node (ref "SATA0") (pin "S6") (pinfunction "S6_S6") (pintype "passive"))
      (node (ref "SATA0") (pin "THT6") (pinfunction "S6_THT6") (pintype "passive"))
      (node (ref "SFF-8087") (pin "A2") (pinfunction "A2_A2") (pintype "passive"))
    )
    (net (code "17") (name "RX1_N") (class "Default")
      (node (ref "SATA1") (pin "S5") (pinfunction "S5_S5") (pintype "passive"))
      (node (ref "SATA1") (pin "THT5") (pinfunction "S5_THT5") (pintype "passive"))
      (node (ref "SFF-8087") (pin "A6") (pinfunction "A6_A6") (pintype "passive"))
    )
    (net (code "18") (name "RX1_P") (class "Default")
      (node (ref "SATA1") (pin "S6") (pinfunction "S6_S6") (pintype "passive"))
      (node (ref "SATA1") (pin "THT6") (pinfunction "S6_THT6") (pintype "passive"))
      (node (ref "SFF-8087") (pin "A5") (pinfunction "A5_A5") (pintype "passive"))
    )
    (net (code "19") (name "RX2_N") (class "Default")
      (node (ref "SATA2") (pin "S5") (pinfunction "S5_S5") (pintype "passive"))
      (node (ref "SATA2") (pin "THT5") (pinfunction "S5_THT5") (pintype "passive"))
      (node (ref "SFF-8087") (pin "A14") (pinfunction "A14_A14") (pintype "passive"))
    )
    (net (code "20") (name "RX2_P") (class "Default")
      (node (ref "SATA2") (pin "S6") (pinfunction "S6_S6") (pintype "passive"))
      (node (ref "SATA2") (pin "THT6") (pinfunction "S6_THT6") (pintype "passive"))
      (node (ref "SFF-8087") (pin "A13") (pinfunction "A13_A13") (pintype "passive"))
    )
    (net (code "21") (name "RX3_N") (class "Default")
      (node (ref "SATA3") (pin "S5") (pinfunction "S5_S5") (pintype "passive"))
      (node (ref "SATA3") (pin "THT5") (pinfunction "S5_THT5") (pintype "passive"))
      (node (ref "SFF-8087") (pin "A17") (pinfunction "A17_A17") (pintype "passive"))
    )
    (net (code "22") (name "RX3_P") (class "Default")
      (node (ref "SATA3") (pin "S6") (pinfunction "S6_S6") (pintype "passive"))
      (node (ref "SATA3") (pin "THT6") (pinfunction "S6_THT6") (pintype "passive"))
      (node (ref "SFF-8087") (pin "A16") (pinfunction "A16_A16") (pintype "passive"))
    )
    (net (code "23") (name "TX0_N") (class "Default")
      (node (ref "SATA0") (pin "S3") (pinfunction "S3_S3") (pintype "passive"))
      (node (ref "SATA0") (pin "THT3") (pinfunction "S3_THT3") (pintype "passive"))
      (node (ref "SFF-8087") (pin "B3") (pinfunction "B3_B3") (pintype "passive"))
    )
    (net (code "24") (name "TX0_P") (class "Default")
      (node (ref "SATA0") (pin "S2") (pinfunction "S2_S2") (pintype "passive"))
      (node (ref "SATA0") (pin "THT2") (pinfunction "S2_THT2") (pintype "passive"))
      (node (ref "SFF-8087") (pin "B2") (pinfunction "B2_B2") (pintype "passive"))
    )
    (net (code "25") (name "TX1_N") (class "Default")
      (node (ref "SATA1") (pin "S3") (pinfunction "S3_S3") (pintype "passive"))
      (node (ref "SATA1") (pin "THT3") (pinfunction "S3_THT3") (pintype "passive"))
      (node (ref "SFF-8087") (pin "B6") (pinfunction "B6_B6") (pintype "passive"))
    )
    (net (code "26") (name "TX1_P") (class "Default")
      (node (ref "SATA1") (pin "S2") (pinfunction "S2_S2") (pintype "passive"))
      (node (ref "SATA1") (pin "THT2") (pinfunction "S2_THT2") (pintype "passive"))
      (node (ref "SFF-8087") (pin "B5") (pinfunction "B5_B5") (pintype "passive"))
    )
    (net (code "27") (name "TX2_N") (class "Default")
      (node (ref "SATA2") (pin "S3") (pinfunction "S3_S3") (pintype "passive"))
      (node (ref "SATA2") (pin "THT3") (pinfunction "S3_THT3") (pintype "passive"))
      (node (ref "SFF-8087") (pin "B14") (pinfunction "B14_B14") (pintype "passive"))
    )
    (net (code "28") (name "TX2_P") (class "Default")
      (node (ref "SATA2") (pin "S2") (pinfunction "S2_S2") (pintype "passive"))
      (node (ref "SATA2") (pin "THT2") (pinfunction "S2_THT2") (pintype "passive"))
      (node (ref "SFF-8087") (pin "B13") (pinfunction "B13_B13") (pintype "passive"))
    )
    (net (code "29") (name "TX3_N") (class "Default")
      (node (ref "SATA3") (pin "S3") (pinfunction "S3_S3") (pintype "passive"))
      (node (ref "SATA3") (pin "THT3") (pinfunction "S3_THT3") (pintype "passive"))
      (node (ref "SFF-8087") (pin "B17") (pinfunction "B17_B17") (pintype "passive"))
    )
    (net (code "30") (name "TX3_P") (class "Default")
      (node (ref "SATA3") (pin "S2") (pinfunction "S2_S2") (pintype "passive"))
      (node (ref "SATA3") (pin "THT2") (pinfunction "S2_THT2") (pintype "passive"))
      (node (ref "SFF-8087") (pin "B16") (pinfunction "B16_B16") (pintype "passive"))
    )
    (net (code "31") (name "unconnected-(FAN_1-Pad3)") (class "Default")
      (node (ref "FAN_1") (pin "3") (pinfunction "3_3") (pintype "passive"))
    )
    (net (code "32") (name "unconnected-(J3-Pad3)") (class "Default")
      (node (ref "J3") (pin "3") (pinfunction "3_3") (pintype "passive"))
    )
    (net (code "33") (name "unconnected-(J4-Pad3)") (class "Default")
      (node (ref "J4") (pin "3") (pinfunction "3_3") (pintype "passive"))
    )
    (net (code "34") (name "unconnected-(PWM_IN-Pad2)") (class "Default")
      (node (ref "PWM_IN") (pin "2") (pinfunction "2_2") (pintype "passive"))
    )
    (net (code "35") (name "unconnected-(SFF-8087-PadA8)") (class "Default")
      (node (ref "SFF-8087") (pin "A8") (pinfunction "A8_A8") (pintype "passive"))
    )
    (net (code "36") (name "unconnected-(SFF-8087-PadA9)") (class "Default")
      (node (ref "SFF-8087") (pin "A9") (pinfunction "A9_A9") (pintype "passive"))
    )
    (net (code "37") (name "unconnected-(SFF-8087-PadA10)") (class "Default")
      (node (ref "SFF-8087") (pin "A10") (pinfunction "A10_A10") (pintype "passive"))
    )
    (net (code "38") (name "unconnected-(SFF-8087-PadA11)") (class "Default")
      (node (ref "SFF-8087") (pin "A11") (pinfunction "A11_A11") (pintype "passive"))
    )
    (net (code "39") (name "unconnected-(SFF-8087-PadB8)") (class "Default")
      (node (ref "SFF-8087") (pin "B8") (pinfunction "B8_B8") (pintype "passive"))
    )
    (net (code "40") (name "unconnected-(SFF-8087-PadB9)") (class "Default")
      (node (ref "SFF-8087") (pin "B9") (pinfunction "B9_B9") (pintype "passive"))
    )
    (net (code "41") (name "unconnected-(SFF-8087-PadB10)") (class "Default")
      (node (ref "SFF-8087") (pin "B10") (pinfunction "B10_B10") (pintype "passive"))
    )
    (net (code "42") (name "unconnected-(SFF-8087-PadB11)") (class "Default")
      (node (ref "SFF-8087") (pin "B11") (pinfunction "B11_B11") (pintype "passive"))
    )
  )
)
